# main.net
KiCad netlist of a schematic drawn in Altium Designer
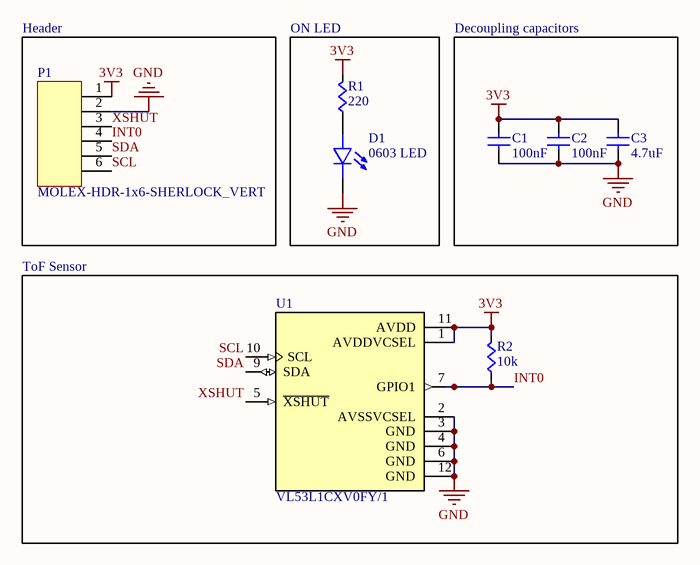
[diagram p0: main.SchDoc]

(export (version "E")
  (design (tool "Eeschema 10.0.6"))
  (components
    (comp (ref "C1")
      (value "100nF")
      (footprint "CAPC0603")
      (fields (field (name "Comment") "Cap"))
      (libsource (lib "Passives") (part "Cap"))
    )
    (comp (ref "C2")
      (value "100nF")
      (footprint "CAPC0603")
      (fields (field (name "Comment") "Cap"))
      (libsource (lib "Passives") (part "Cap"))
    )
    (comp (ref "C3")
      (value "4.7uF")
      (footprint "CAPC0603")
      (fields (field (name "Comment") "Cap"))
      (libsource (lib "Passives") (part "Cap"))
    )
    (comp (ref "D1")
      (value "0603 LED")
      (footprint "0603 (LED)")
      (description "150060SS75000 ¦ LED Indication - Discrete 1.9V 0603 (1608 Metric)")
      (libsource (lib "Alexandria") (part "0603 LED"))
    )
    (comp (ref "P1")
      (value "MOLEX-HDR-1x6-SHERLOCK_VERT")
      (footprint "MOLEX-HDR-1X6-SHERLOCK-VERT")
      (libsource (lib "Connectors") (part "MOLEX-HDR-1x6-SHERLOCK_VERT"))
    )
    (comp (ref "R1")
      (value "220")
      (footprint "RES0603")
      (description "SMD, RES0603")
      (fields (field (name "Comment") "Res"))
      (libsource (lib "Passives") (part "Res"))
    )
    (comp (ref "R2")
      (value "10k")
      (footprint "RES0603")
      (description "SMD, RES0603")
      (fields (field (name "Comment") "Res"))
      (libsource (lib "Passives") (part "Res"))
    )
    (comp (ref "U1")
      (value "VL53L1CXV0FY/1")
      (footprint "LGA-12 (VL53L1CXV0FY/1)")
      (description "ToF Optical Sensor 157.480 (4m) I²C Output from STMelectronics")
      (fields (field (name "MF") "STMicroelectronics"))
      (libsource (lib "Alexandria") (part "VL53L1CXV0FY/1"))
    )
  )
  (nets
    (net (code "1") (name "/INT0") (class "Default")
      (node (ref "P1") (pin "4") (pinfunction "4_4") (pintype "passive"))
      (node (ref "R2") (pin "2") (pinfunction "B_2") (pintype "passive"))
      (node (ref "U1") (pin "7") (pinfunction "GPIO1_7") (pintype "output"))
    )
    (net (code "2") (name "/SCL") (class "Default")
      (node (ref "P1") (pin "6") (pinfunction "6_6") (pintype "passive"))
      (node (ref "U1") (pin "10") (pinfunction "SCL_10") (pintype "input"))
    )
    (net (code "3") (name "/SDA") (class "Default")
      (node (ref "P1") (pin "5") (pinfunction "5_5") (pintype "passive"))
      (node (ref "U1") (pin "9") (pinfunction "SDA_9") (pintype "bidirectional"))
    )
    (net (code "4") (name "/XSHUT") (class "Default")
      (node (ref "P1") (pin "3") (pinfunction "3_3") (pintype "passive"))
      (node (ref "U1") (pin "5") (pinfunction "~{XSHUT}_5") (pintype "input"))
    )
    (net (code "5") (name "3V3") (class "Default")
      (node (ref "C1") (pin "1") (pinfunction "A_1") (pintype "passive"))
      (node (ref "C2") (pin "1") (pinfunction "A_1") (pintype "passive"))
      (node (ref "C3") (pin "1") (pinfunction "A_1") (pintype "passive"))
      (node (ref "P1") (pin "1") (pinfunction "1_1") (pintype "passive"))
      (node (ref "R1") (pin "1") (pinfunction "A_1") (pintype "passive"))
      (node (ref "R2") (pin "1") (pinfunction "A_1") (pintype "passive"))
      (node (ref "U1") (pin "1") (pinfunction "AVDDVCSEL_1") (pintype "power_in"))
      (node (ref "U1") (pin "11") (pinfunction "AVDD_11") (pintype "power_in"))
    )
    (net (code "6") (name "GND") (class "Default")
      (node (ref "C1") (pin "2") (pinfunction "B_2") (pintype "passive"))
      (node (ref "C2") (pin "2") (pinfunction "B_2") (pintype "passive"))
      (node (ref "C3") (pin "2") (pinfunction "B_2") (pintype "passive"))
      (node (ref "D1") (pin "C") (pinfunction "C_C") (pintype "passive"))
      (node (ref "P1") (pin "2") (pinfunction "2_2") (pintype "passive"))
      (node (ref "U1") (pin "12") (pinfunction "GND_12") (pintype "power_in"))
      (node (ref "U1") (pin "2") (pinfunction "AVSSVCSEL_2") (pintype "power_in"))
      (node (ref "U1") (pin "3") (pinfunction "GND_3") (pintype "power_in"))
      (node (ref "U1") (pin "4") (pinfunction "GND_4") (pintype "power_in"))
      (node (ref "U1") (pin "6") (pinfunction "GND_6") (pintype "power_in"))
    )
    (net (code "7") (name "Net-(R1-B)") (class "Default")
      (node (ref "D1") (pin "A") (pinfunction "A_A") (pintype "passive"))
      (node (ref "R1") (pin "2") (pinfunction "B_2") (pintype "passive"))
    )
  )
)
